# 12_-_SD.net
KiCad netlist of a schematic drawn in Altium Designer
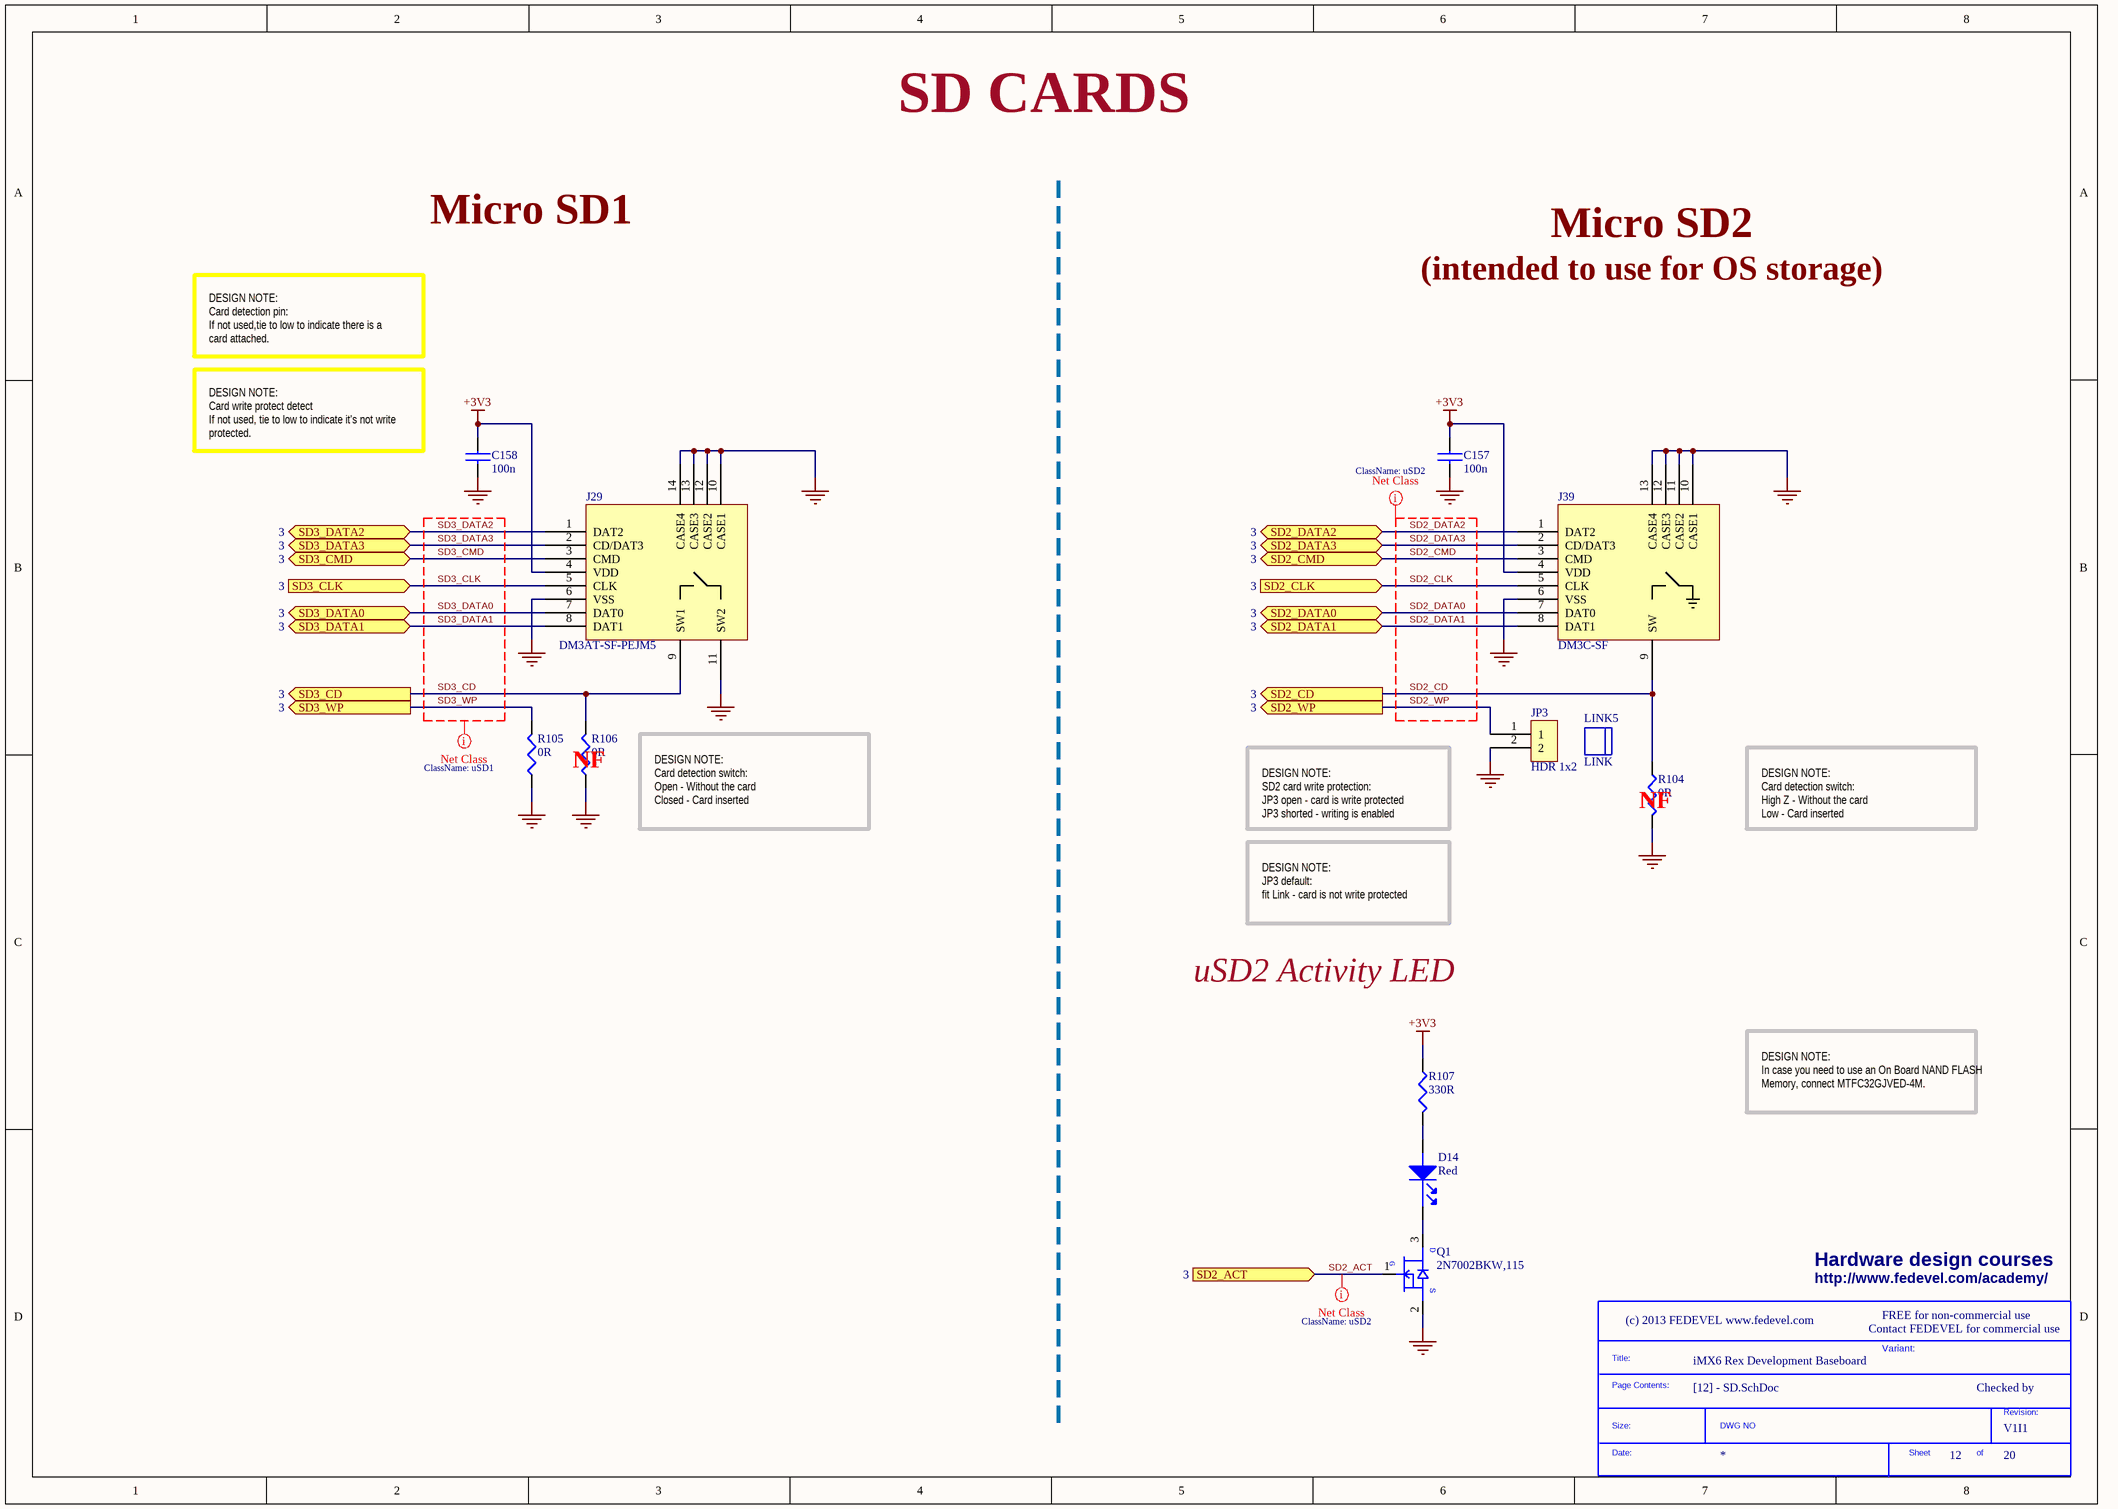
[diagram p0: [12] - SD.SchDoc]

(export (version "E")
  (design (tool "Eeschema 10.0.6"))
  (components
    (comp (ref "C157")
      (value "100n")
      (footprint "C0402")
      (description "CAP CER .10UF 50V X5R 10% 0402")
      (fields
        (field (name "MANUFACTURER") "TDK Corporation")
        (field (name "MANUFACTURER PART NUMBER") "C1005X5R1H104K")
      )
      (libsource (lib "Integrated_Library_RF_FEB_2012") (part "C1005X5R1H104K"))
    )
    (comp (ref "C158")
      (value "100n")
      (footprint "C0402")
      (description "CAP CER .10UF 50V X5R 10% 0402")
      (fields
        (field (name "MANUFACTURER") "TDK Corporation")
        (field (name "MANUFACTURER PART NUMBER") "C1005X5R1H104K")
      )
      (libsource (lib "Integrated_Library_RF_FEB_2012") (part "C1005X5R1H104K"))
    )
    (comp (ref "D14")
      (value "Red")
      (footprint "LED_0603")
      (description "LED SMARTLED RED 630NM 0603 SMD")
      (fields
        (field (name "MANUFACTURER") "OSRAM Opto Semiconductors Inc")
        (field (name "MANUFACTURER PART NUMBER") "LS L29K-H1J2-1-Z")
        (field (name ".CHECKED PCB") "RF")
        (field (name ".CHECKED SCH") "RF")
      )
      (libsource (lib "Integrated_Library_RF_FEB_2012") (part "LS L29K-H1J2-1-Z"))
    )
    (comp (ref "J29")
      (value "DM3AT-SF-PEJM5")
      (footprint "uSD_DM3AT")
      (description "CONN MICRO SD R/A PUSH-PUSH SMD")
      (fields
        (field (name "MANUFACTURER") "Hirose Electric Co Ltd")
        (field (name ".CHECKED PCB") "MM")
        (field (name ".CHECKED SCH") "MM")
      )
      (libsource (lib "Integrated_Library_RF_FEB_2012") (part "DM3AT-SF-PEJM5"))
    )
    (comp (ref "J39")
      (value "DM3C-SF")
      (footprint "uSD_DM3CS")
      (description "CONN MICRO SD R/A HING TYPE SMD")
      (fields
        (field (name "MANUFACTURER") "Hirose Electric Co Ltd")
        (field (name ".CREATOR") "MM")
        (field (name ".CHECKED PCB") "MM")
        (field (name ".CHECKED SCH") "MM")
      )
      (libsource (lib "Integrated_Library_RF_FEB_2012") (part "DM3C-SF"))
    )
    (comp (ref "JP3")
      (value "HDR 1x2")
      (footprint "HDR_1x2_2.54MM")
      (description "BERGSTIK II .100\" SR STRAIGHT")
      (fields
        (field (name "MANUFACTURER") "FCI")
        (field (name "MANUFACTURER PART NUMBER") "68001-202HLF")
        (field (name ".CHECKED PCB") "RF")
        (field (name ".CHECKED SCH") "RF")
      )
      (libsource (lib "Integrated_Library_RF_FEB_2012") (part "68001-202HLF"))
    )
    (comp (ref "LINK5")
      (value "LINK")
      (description "CONN JUMPER SHORTING .100\" GOLD")
      (fields
        (field (name "MANUFACTURER") "Sullins Connector Solutions")
        (field (name "MANUFACTURER PART NUMBER") "QPC02SXGN-RC")
        (field (name ".CHECKED SCH") "RF")
      )
      (libsource (lib "Integrated_Library_RF_FEB_2012") (part "QPC02SXGN-RC"))
    )
    (comp (ref "Q1")
      (value "2N7002BKW,115")
      (footprint "SC70_SOT323")
      (description "MOSFET N-CH 60V 310MA SOT323")
      (fields
        (field (name "MANUFACTURER") "NXP Semiconductors")
        (field (name ".CHECKED PCB") "RF")
        (field (name ".CHECKED SCH") "RF")
      )
      (libsource (lib "Integrated_Library_RF_FEB_2012") (part "2N7002BKW,115"))
    )
    (comp (ref "R104")
      (value "0R")
      (footprint "R0402")
      (description "RES 0.0 OHM 1/16W 0402 SMD")
      (fields
        (field (name "MANUFACTURER") "Yageo")
        (field (name "MANUFACTURER PART NUMBER") "RC0402JR-070RL")
      )
      (libsource (lib "Integrated_Library_RF_FEB_2012") (part "RC0402JR-070RL"))
    )
    (comp (ref "R105")
      (value "0R")
      (footprint "R0402")
      (description "RES 0.0 OHM 1/16W 0402 SMD")
      (fields
        (field (name "MANUFACTURER") "Yageo")
        (field (name "MANUFACTURER PART NUMBER") "RC0402JR-070RL")
      )
      (libsource (lib "Integrated_Library_RF_FEB_2012") (part "RC0402JR-070RL"))
    )
    (comp (ref "R106")
      (value "0R")
      (footprint "R0402")
      (description "RES 0.0 OHM 1/16W 0402 SMD")
      (fields
        (field (name "MANUFACTURER") "Yageo")
        (field (name "MANUFACTURER PART NUMBER") "RC0402JR-070RL")
      )
      (libsource (lib "Integrated_Library_RF_FEB_2012") (part "RC0402JR-070RL"))
    )
    (comp (ref "R107")
      (value "330R")
      (footprint "R0402")
      (description "RES 330 OHM 1/16W 1% 0402 SMD")
      (fields
        (field (name "MANUFACTURER") "Vishay Dale")
        (field (name "MANUFACTURER PART NUMBER") "CRCW0402330RFKED")
        (field (name ".CHECKED PCB") "RF")
        (field (name ".CHECKED SCH") "RF")
      )
      (libsource (lib "Integrated_Library_RF_FEB_2012") (part "CRCW0402330RFKED"))
    )
  )
  (nets
    (net (code "1") (name "+3V3") (class "Default")
      (node (ref "C157") (pin "1") (pinfunction "1_1") (pintype "passive"))
      (node (ref "C158") (pin "1") (pinfunction "1_1") (pintype "passive"))
      (node (ref "J29") (pin "4") (pinfunction "VDD_4") (pintype "passive"))
      (node (ref "J39") (pin "4") (pinfunction "VDD_4") (pintype "passive"))
      (node (ref "R107") (pin "1") (pinfunction "1_1") (pintype "passive"))
    )
    (net (code "2") (name "/SD2_ACT") (class "Default")
      (node (ref "Q1") (pin "1") (pinfunction "GATE_1") (pintype "passive"))
    )
    (net (code "3") (name "/SD2_CD") (class "Default")
      (node (ref "J39") (pin "9") (pinfunction "SW_9") (pintype "passive"))
      (node (ref "R104") (pin "2") (pinfunction "2_2") (pintype "passive"))
    )
    (net (code "4") (name "/SD2_CLK") (class "Default")
      (node (ref "J39") (pin "5") (pinfunction "CLK_5") (pintype "passive"))
    )
    (net (code "5") (name "/SD2_CMD") (class "Default")
      (node (ref "J39") (pin "3") (pinfunction "CMD_3") (pintype "passive"))
    )
    (net (code "6") (name "/SD2_DATA0") (class "Default")
      (node (ref "J39") (pin "7") (pinfunction "DAT0_7") (pintype "passive"))
    )
    (net (code "7") (name "/SD2_DATA1") (class "Default")
      (node (ref "J39") (pin "8") (pinfunction "DAT1_8") (pintype "passive"))
    )
    (net (code "8") (name "/SD2_DATA2") (class "Default")
      (node (ref "J39") (pin "1") (pinfunction "DAT2_1") (pintype "passive"))
    )
    (net (code "9") (name "/SD2_DATA3") (class "Default")
      (node (ref "J39") (pin "2") (pinfunction "CD/DAT3_2") (pintype "passive"))
    )
    (net (code "10") (name "/SD2_WP") (class "Default")
      (node (ref "JP3") (pin "1") (pinfunction "1_1") (pintype "passive"))
    )
    (net (code "11") (name "/SD3_CD") (class "Default")
      (node (ref "J29") (pin "9") (pinfunction "SW1_9") (pintype "passive"))
      (node (ref "R106") (pin "2") (pinfunction "2_2") (pintype "passive"))
    )
    (net (code "12") (name "/SD3_CLK") (class "Default")
      (node (ref "J29") (pin "5") (pinfunction "CLK_5") (pintype "passive"))
    )
    (net (code "13") (name "/SD3_CMD") (class "Default")
      (node (ref "J29") (pin "3") (pinfunction "CMD_3") (pintype "passive"))
    )
    (net (code "14") (name "/SD3_DATA0") (class "Default")
      (node (ref "J29") (pin "7") (pinfunction "DAT0_7") (pintype "passive"))
    )
    (net (code "15") (name "/SD3_DATA1") (class "Default")
      (node (ref "J29") (pin "8") (pinfunction "DAT1_8") (pintype "passive"))
    )
    (net (code "16") (name "/SD3_DATA2") (class "Default")
      (node (ref "J29") (pin "1") (pinfunction "DAT2_1") (pintype "passive"))
    )
    (net (code "17") (name "/SD3_DATA3") (class "Default")
      (node (ref "J29") (pin "2") (pinfunction "CD/DAT3_2") (pintype "passive"))
    )
    (net (code "18") (name "/SD3_WP") (class "Default")
      (node (ref "R105") (pin "2") (pinfunction "2_2") (pintype "passive"))
    )
    (net (code "19") (name "GND") (class "Default")
      (node (ref "C157") (pin "2") (pinfunction "2_2") (pintype "passive"))
      (node (ref "C158") (pin "2") (pinfunction "2_2") (pintype "passive"))
      (node (ref "J29") (pin "10") (pinfunction "CASE1_10") (pintype "passive"))
      (node (ref "J29") (pin "11") (pinfunction "SW2_11") (pintype "passive"))
      (node (ref "J29") (pin "12") (pinfunction "CASE2_12") (pintype "passive"))
      (node (ref "J29") (pin "13") (pinfunction "CASE3_13") (pintype "passive"))
      (node (ref "J29") (pin "14") (pinfunction "CASE4_14") (pintype "passive"))
      (node (ref "J29") (pin "6") (pinfunction "VSS_6") (pintype "passive"))
      (node (ref "J39") (pin "10") (pinfunction "CASE1_10") (pintype "passive"))
      (node (ref "J39") (pin "11") (pinfunction "CASE2_11") (pintype "passive"))
      (node (ref "J39") (pin "12") (pinfunction "CASE3_12") (pintype "passive"))
      (node (ref "J39") (pin "13") (pinfunction "CASE4_13") (pintype "passive"))
      (node (ref "J39") (pin "6") (pinfunction "VSS_6") (pintype "passive"))
      (node (ref "JP3") (pin "2") (pinfunction "2_2") (pintype "passive"))
      (node (ref "Q1") (pin "2") (pinfunction "SOURCE_2") (pintype "passive"))
      (node (ref "R104") (pin "1") (pinfunction "1_1") (pintype "passive"))
      (node (ref "R105") (pin "1") (pinfunction "1_1") (pintype "passive"))
      (node (ref "R106") (pin "1") (pinfunction "1_1") (pintype "passive"))
    )
    (net (code "20") (name "Net-(D14-ANODE)") (class "Default")
      (node (ref "D14") (pin "2") (pinfunction "ANODE_2") (pintype "passive"))
      (node (ref "R107") (pin "2") (pinfunction "2_2") (pintype "passive"))
    )
    (net (code "21") (name "Net-(D14-cathode)") (class "Default")
      (node (ref "D14") (pin "1") (pinfunction "cathode_1") (pintype "passive"))
      (node (ref "Q1") (pin "3") (pinfunction "DRAIN_3") (pintype "passive"))
    )
  )
)
